# Connectors_GPIOs.net
KiCad netlist of a schematic drawn in Altium Designer
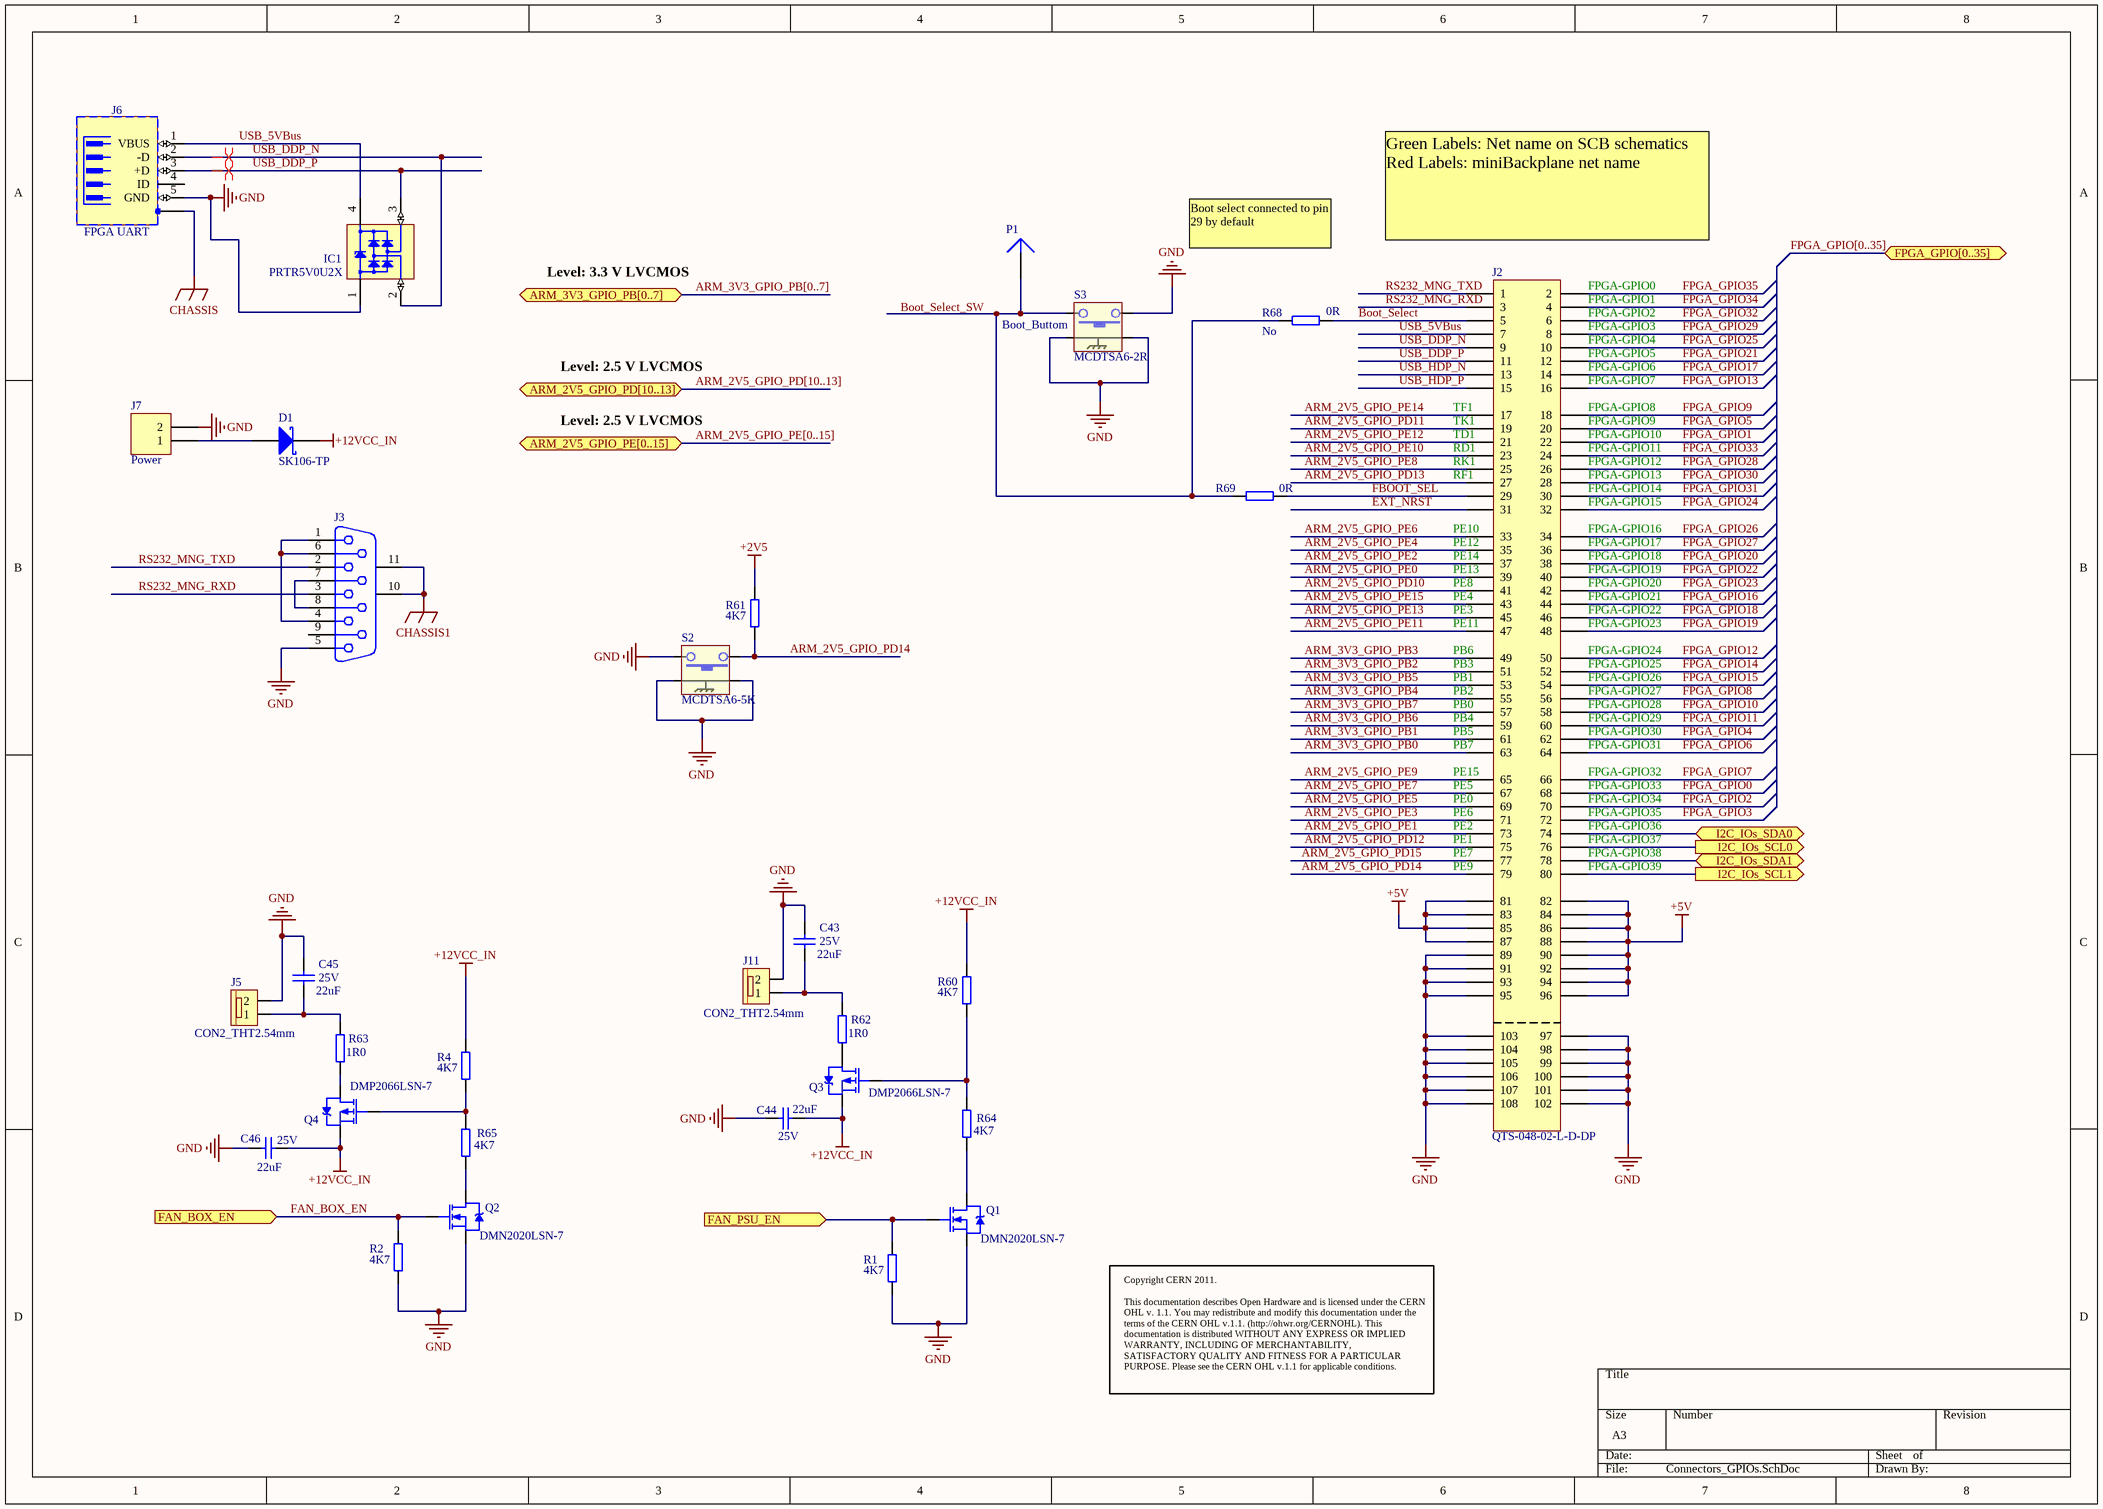
[diagram p0: Connectors_GPIOs.SchDoc]

(export (version "E")
  (design (tool "Eeschema 10.0.6"))
  (components
    (comp (ref "C43")
      (value "22uF")
      (footprint "CC3216-1206")
      (description "Capacitor")
      (fields
        (field (name "TOLERANCE") "±10%")
        (field (name "VOLTAGE") "25V")
        (field (name "Comment") "22uF 25V")
        (field (name "PUBLISHER") "Altium Limited")
      )
      (libsource (lib "wr_switch") (part "Cap"))
    )
    (comp (ref "C44")
      (value "22uF")
      (footprint "CC3216-1206")
      (description "Capacitor")
      (fields
        (field (name "TOLERANCE") "±10%")
        (field (name "VOLTAGE") "25V")
        (field (name "Comment") "22uF 25V")
        (field (name "PUBLISHER") "Altium Limited")
      )
      (libsource (lib "wr_switch") (part "Cap"))
    )
    (comp (ref "C45")
      (value "22uF")
      (footprint "CC3216-1206")
      (description "Capacitor")
      (fields
        (field (name "TOLERANCE") "±10%")
        (field (name "VOLTAGE") "25V")
        (field (name "Comment") "22uF 25V")
        (field (name "PUBLISHER") "Altium Limited")
      )
      (libsource (lib "wr_switch") (part "Cap"))
    )
    (comp (ref "C46")
      (value "22uF")
      (footprint "CC3216-1206")
      (description "Capacitor")
      (fields
        (field (name "TOLERANCE") "±10%")
        (field (name "VOLTAGE") "25V")
        (field (name "Comment") "22uF 25V")
        (field (name "PUBLISHER") "Altium Limited")
      )
      (libsource (lib "wr_switch") (part "Cap"))
    )
    (comp (ref "D1")
      (value "SK106-TP")
      (footprint "7S_WR:DO-214AB/SMB-MCC")
      (description "Schottky Diode 10A 60V")
      (libsource (lib "wr_switch") (part "SK106-TP"))
    )
    (comp (ref "IC1")
      (value "PRTR5V0U2X")
      (footprint "7S_WR:SOT190P230X110-4N")
      (description "Ultra Low Capacitance Double Rail-to-Rail ESD Protection Diode")
      (fields
        (field (name "VOLTAGE") "5.5V")
        (field (name "MANUFACTURER") "PHILIPS NXP")
        (field (name "AUTHOR") "CERN DEM JLC")
      )
      (libsource (lib "wr_switch") (part "PRTR5V0U2X"))
    )
    (comp (ref "J2")
      (value "QTS-048-02-L-D-DP")
      (footprint "QTS-048-XX-X-D-DP-A")
      (description "High Speed Ground Plane Header")
      (libsource (lib "wr_switch") (part "QTS-048-01-L-D-DP"))
    )
    (comp (ref "J3")
      (value "D Connector 9")
      (footprint "7S_WR:DSUB1.385-2H9")
      (description "Receptacle Assembly, 9 Position, Right Angle")
      (fields (field (name "PUBLISHER") "Altium Limited"))
      (libsource (lib "Miscellaneous Connectors") (part "D Connector 9"))
    )
    (comp (ref "J5")
      (value "CON2_THT2.54mm")
      (footprint "Wurth_619_0xx")
      (description "Connector")
      (libsource (lib "wr_switch") (part "CON2_619_0xx"))
    )
    (comp (ref "J6")
      (value "FPGA UART")
      (footprint "7S_WR:TYCO_1734035-1")
      (description "5 Pin + 1 Shield USB Receptacle")
      (fields
        (field (name "PART NUMBER") "TYCO_1734035-1")
        (field (name "MANUFACTURER") "TYCO ELECTRONICS")
        (field (name "AUTHOR") "CERN DEM JLC")
      )
      (libsource (lib "Connectors") (part "Connector USB 5 Pin + 1Shield"))
    )
    (comp (ref "J7")
      (value "Power")
      (footprint "7S_WR:TYCO_794120_1")
      (description "Header, 2-Pin")
      (fields (field (name "PUBLISHER") "Altium Limited"))
      (libsource (lib "Miscellaneous Connectors") (part "Header 2"))
    )
    (comp (ref "J11")
      (value "CON2_THT2.54mm")
      (footprint "Wurth_619_0xx")
      (description "Connector")
      (libsource (lib "wr_switch") (part "CON2_619_0xx"))
    )
    (comp (ref "P1")
      (value "Boot_Buttom")
      (footprint "PIN1-RT-01T-1.0B(LF)")
      (description "Plug")
      (fields (field (name "PUBLISHER") "Altium Limited"))
      (libsource (lib "Miscellaneous Connectors") (part "Plug"))
    )
    (comp (ref "Q1")
      (value "DMN2020LSN-7")
      (footprint "7S_WR:SC-59-3")
      (description "N-Channel Power MOSFET")
      (fields (field (name "MANUFACTURER") "Diodes Inc.") (field (name "PUBLISHER") "Altium Limited"))
      (libsource (lib "wr_switch") (part "NMOS-2"))
    )
    (comp (ref "Q2")
      (value "DMN2020LSN-7")
      (footprint "7S_WR:SC-59-3")
      (description "N-Channel Power MOSFET")
      (fields (field (name "MANUFACTURER") "Diodes Inc.") (field (name "PUBLISHER") "Altium Limited"))
      (libsource (lib "wr_switch") (part "NMOS-2"))
    )
    (comp (ref "Q3")
      (value "DMP2066LSN-7")
      (footprint "SC-59-3")
      (description "P-Channel Enhancement MOSFET")
      (fields (field (name "MANUFACTURER") "Diodes Inc."))
      (libsource (lib "wr_switch") (part "PMOS-2-Reflexion"))
    )
    (comp (ref "Q4")
      (value "DMP2066LSN-7")
      (footprint "SC-59-3")
      (description "P-Channel Enhancement MOSFET")
      (fields (field (name "MANUFACTURER") "Diodes Inc."))
      (libsource (lib "wr_switch") (part "PMOS-2-Reflexion"))
    )
    (comp (ref "R1")
      (value "4K7")
      (footprint "0603")
      (description "SMD Resistor")
      (fields (field (name "TOLERANCE") "±1%"))
      (libsource (lib "wr_switch") (part "RES_SMD"))
    )
    (comp (ref "R2")
      (value "4K7")
      (footprint "0603")
      (description "SMD Resistor")
      (fields (field (name "TOLERANCE") "±1%"))
      (libsource (lib "wr_switch") (part "RES_SMD"))
    )
    (comp (ref "R4")
      (value "4K7")
      (footprint "0603")
      (description "SMD Resistor")
      (fields (field (name "TOLERANCE") "±1%"))
      (libsource (lib "wr_switch") (part "RES_SMD"))
    )
    (comp (ref "R60")
      (value "4K7")
      (footprint "0603")
      (description "SMD Resistor")
      (fields (field (name "TOLERANCE") "±1%"))
      (libsource (lib "wr_switch") (part "RES_SMD"))
    )
    (comp (ref "R61")
      (value "4K7")
      (footprint "0603")
      (description "SMD Resistor")
      (fields (field (name "TOLERANCE") "±1%"))
      (libsource (lib "wr_switch") (part "RES_SMD"))
    )
    (comp (ref "R62")
      (value "1R0")
      (footprint "CR3225-1210")
      (description "SMD Resistor")
      (fields (field (name "TOLERANCE") "±1%"))
      (libsource (lib "wr_switch") (part "RES_SMD"))
    )
    (comp (ref "R63")
      (value "1R0")
      (footprint "CR3225-1210")
      (description "SMD Resistor")
      (fields (field (name "TOLERANCE") "±1%"))
      (libsource (lib "wr_switch") (part "RES_SMD"))
    )
    (comp (ref "R64")
      (value "4K7")
      (footprint "0603")
      (description "SMD Resistor")
      (fields (field (name "TOLERANCE") "±1%"))
      (libsource (lib "wr_switch") (part "RES_SMD"))
    )
    (comp (ref "R65")
      (value "4K7")
      (footprint "0603")
      (description "SMD Resistor")
      (fields (field (name "TOLERANCE") "±1%"))
      (libsource (lib "wr_switch") (part "RES_SMD"))
    )
    (comp (ref "R68")
      (value "0R")
      (footprint "0603")
      (description "SMD Resistor")
      (fields (field (name "MOUNTED") "No"))
      (libsource (lib "wr_switch") (part "RES_SMD"))
    )
    (comp (ref "R69")
      (value "0R")
      (footprint "0603")
      (description "SMD Resistor")
      (libsource (lib "wr_switch") (part "RES_SMD"))
    )
    (comp (ref "S2")
      (value "MCDTSA6-5K")
      (footprint "MCDTSA6")
      (description "Push button SPNO Right Angle Through Hole")
      (libsource (lib "wr_switch") (part "MCDTSA6"))
    )
    (comp (ref "S3")
      (value "MCDTSA6-2R")
      (footprint "MCDTSA6")
      (description "Push button SPNO Right Angle Through Hole")
      (libsource (lib "wr_switch") (part "MCDTSA6"))
    )
  )
  (nets
    (net (code "1") (name "+2V5") (class "Default")
      (node (ref "R61") (pin "1") (pinfunction "1_1") (pintype "passive"))
    )
    (net (code "2") (name "+5V") (class "Default")
      (node (ref "J2") (pin "81") (pinfunction "81_81") (pintype "passive"))
      (node (ref "J2") (pin "82") (pinfunction "82_82") (pintype "passive"))
      (node (ref "J2") (pin "83") (pinfunction "83_83") (pintype "passive"))
      (node (ref "J2") (pin "84") (pinfunction "84_84") (pintype "passive"))
      (node (ref "J2") (pin "85") (pinfunction "85_85") (pintype "passive"))
      (node (ref "J2") (pin "86") (pinfunction "86_86") (pintype "passive"))
      (node (ref "J2") (pin "87") (pinfunction "87_87") (pintype "passive"))
      (node (ref "J2") (pin "88") (pinfunction "88_88") (pintype "passive"))
      (node (ref "J2") (pin "90") (pinfunction "90_90") (pintype "passive"))
      (node (ref "J2") (pin "92") (pinfunction "92_92") (pintype "passive"))
      (node (ref "J2") (pin "94") (pinfunction "94_94") (pintype "passive"))
      (node (ref "J2") (pin "96") (pinfunction "96_96") (pintype "passive"))
    )
    (net (code "3") (name "+12VCC_IN") (class "Default")
      (node (ref "C44") (pin "1") (pinfunction "1_1") (pintype "passive"))
      (node (ref "C46") (pin "1") (pinfunction "1_1") (pintype "passive"))
      (node (ref "D1") (pin "1") (pinfunction "K_1") (pintype "passive"))
      (node (ref "Q3") (pin "3") (pinfunction "S_3") (pintype "passive"))
      (node (ref "Q4") (pin "3") (pinfunction "S_3") (pintype "passive"))
      (node (ref "R4") (pin "1") (pinfunction "1_1") (pintype "passive"))
      (node (ref "R60") (pin "1") (pinfunction "1_1") (pintype "passive"))
    )
    (net (code "4") (name "/ARM_2V5_GPIO_PD10") (class "Default")
      (node (ref "J2") (pin "41") (pinfunction "41_41") (pintype "passive"))
    )
    (net (code "5") (name "/ARM_2V5_GPIO_PD11") (class "Default")
      (node (ref "J2") (pin "19") (pinfunction "19_19") (pintype "passive"))
    )
    (net (code "6") (name "/ARM_2V5_GPIO_PD12") (class "Default")
      (node (ref "J2") (pin "75") (pinfunction "75_75") (pintype "passive"))
    )
    (net (code "7") (name "/ARM_2V5_GPIO_PD13") (class "Default")
      (node (ref "J2") (pin "27") (pinfunction "27_27") (pintype "passive"))
    )
    (net (code "8") (name "/ARM_2V5_GPIO_PD14") (class "Default")
      (node (ref "J2") (pin "79") (pinfunction "79_79") (pintype "passive"))
      (node (ref "R61") (pin "2") (pinfunction "2_2") (pintype "passive"))
      (node (ref "S2") (pin "1") (pinfunction "1_1") (pintype "passive"))
    )
    (net (code "9") (name "/ARM_2V5_GPIO_PD15") (class "Default")
      (node (ref "J2") (pin "77") (pinfunction "77_77") (pintype "passive"))
    )
    (net (code "11") (name "/ARM_2V5_GPIO_PE0") (class "Default")
      (node (ref "J2") (pin "39") (pinfunction "39_39") (pintype "passive"))
    )
    (net (code "12") (name "/ARM_2V5_GPIO_PE1") (class "Default")
      (node (ref "J2") (pin "73") (pinfunction "73_73") (pintype "passive"))
    )
    (net (code "13") (name "/ARM_2V5_GPIO_PE2") (class "Default")
      (node (ref "J2") (pin "37") (pinfunction "37_37") (pintype "passive"))
    )
    (net (code "14") (name "/ARM_2V5_GPIO_PE3") (class "Default")
      (node (ref "J2") (pin "71") (pinfunction "71_71") (pintype "passive"))
    )
    (net (code "15") (name "/ARM_2V5_GPIO_PE4") (class "Default")
      (node (ref "J2") (pin "35") (pinfunction "35_35") (pintype "passive"))
    )
    (net (code "16") (name "/ARM_2V5_GPIO_PE5") (class "Default")
      (node (ref "J2") (pin "69") (pinfunction "69_69") (pintype "passive"))
    )
    (net (code "17") (name "/ARM_2V5_GPIO_PE6") (class "Default")
      (node (ref "J2") (pin "33") (pinfunction "33_33") (pintype "passive"))
    )
    (net (code "18") (name "/ARM_2V5_GPIO_PE7") (class "Default")
      (node (ref "J2") (pin "67") (pinfunction "67_67") (pintype "passive"))
    )
    (net (code "19") (name "/ARM_2V5_GPIO_PE8") (class "Default")
      (node (ref "J2") (pin "25") (pinfunction "25_25") (pintype "passive"))
    )
    (net (code "20") (name "/ARM_2V5_GPIO_PE9") (class "Default")
      (node (ref "J2") (pin "65") (pinfunction "65_65") (pintype "passive"))
    )
    (net (code "21") (name "/ARM_2V5_GPIO_PE10") (class "Default")
      (node (ref "J2") (pin "23") (pinfunction "23_23") (pintype "passive"))
    )
    (net (code "22") (name "/ARM_2V5_GPIO_PE11") (class "Default")
      (node (ref "J2") (pin "47") (pinfunction "47_47") (pintype "passive"))
    )
    (net (code "23") (name "/ARM_2V5_GPIO_PE12") (class "Default")
      (node (ref "J2") (pin "21") (pinfunction "21_21") (pintype "passive"))
    )
    (net (code "24") (name "/ARM_2V5_GPIO_PE13") (class "Default")
      (node (ref "J2") (pin "45") (pinfunction "45_45") (pintype "passive"))
    )
    (net (code "25") (name "/ARM_2V5_GPIO_PE14") (class "Default")
      (node (ref "J2") (pin "17") (pinfunction "17_17") (pintype "passive"))
    )
    (net (code "26") (name "/ARM_2V5_GPIO_PE15") (class "Default")
      (node (ref "J2") (pin "43") (pinfunction "43_43") (pintype "passive"))
    )
    (net (code "28") (name "/ARM_3V3_GPIO_PB0") (class "Default")
      (node (ref "J2") (pin "63") (pinfunction "63_63") (pintype "passive"))
    )
    (net (code "29") (name "/ARM_3V3_GPIO_PB1") (class "Default")
      (node (ref "J2") (pin "61") (pinfunction "61_61") (pintype "passive"))
    )
    (net (code "30") (name "/ARM_3V3_GPIO_PB2") (class "Default")
      (node (ref "J2") (pin "51") (pinfunction "51_51") (pintype "passive"))
    )
    (net (code "31") (name "/ARM_3V3_GPIO_PB3") (class "Default")
      (node (ref "J2") (pin "49") (pinfunction "49_49") (pintype "passive"))
    )
    (net (code "32") (name "/ARM_3V3_GPIO_PB4") (class "Default")
      (node (ref "J2") (pin "55") (pinfunction "55_55") (pintype "passive"))
    )
    (net (code "33") (name "/ARM_3V3_GPIO_PB5") (class "Default")
      (node (ref "J2") (pin "53") (pinfunction "53_53") (pintype "passive"))
    )
    (net (code "34") (name "/ARM_3V3_GPIO_PB6") (class "Default")
      (node (ref "J2") (pin "59") (pinfunction "59_59") (pintype "passive"))
    )
    (net (code "35") (name "/ARM_3V3_GPIO_PB7") (class "Default")
      (node (ref "J2") (pin "57") (pinfunction "57_57") (pintype "passive"))
    )
    (net (code "37") (name "/Boot_Select") (class "Default")
      (node (ref "J2") (pin "5") (pinfunction "5_5") (pintype "passive"))
      (node (ref "R68") (pin "2") (pinfunction "2_2") (pintype "passive"))
    )
    (net (code "39") (name "/EXT_NRST") (class "Default")
      (node (ref "J2") (pin "31") (pinfunction "31_31") (pintype "passive"))
    )
    (net (code "40") (name "/FAN_BOX_EN") (class "Default")
      (node (ref "Q2") (pin "1") (pinfunction "G_1") (pintype "passive"))
      (node (ref "R2") (pin "1") (pinfunction "1_1") (pintype "passive"))
    )
    (net (code "41") (name "/FAN_PSU_EN") (class "Default")
      (node (ref "Q1") (pin "1") (pinfunction "G_1") (pintype "passive"))
      (node (ref "R1") (pin "1") (pinfunction "1_1") (pintype "passive"))
    )
    (net (code "42") (name "/FBOOT_SEL") (class "Default")
      (node (ref "J2") (pin "29") (pinfunction "29_29") (pintype "passive"))
      (node (ref "R69") (pin "2") (pinfunction "2_2") (pintype "passive"))
    )
    (net (code "43") (name "/FPGA-GPIO36") (class "Default")
      (node (ref "J2") (pin "74") (pinfunction "74_74") (pintype "passive"))
    )
    (net (code "44") (name "/FPGA-GPIO37") (class "Default")
      (node (ref "J2") (pin "76") (pinfunction "76_76") (pintype "passive"))
    )
    (net (code "45") (name "/FPGA-GPIO38") (class "Default")
      (node (ref "J2") (pin "78") (pinfunction "78_78") (pintype "passive"))
    )
    (net (code "46") (name "/FPGA-GPIO39") (class "Default")
      (node (ref "J2") (pin "80") (pinfunction "80_80") (pintype "passive"))
    )
    (net (code "47") (name "/FPGA_GPIO0") (class "Default")
      (node (ref "J2") (pin "68") (pinfunction "68_68") (pintype "passive"))
    )
    (net (code "48") (name "/FPGA_GPIO1") (class "Default")
      (node (ref "J2") (pin "22") (pinfunction "22_22") (pintype "passive"))
    )
    (net (code "49") (name "/FPGA_GPIO2") (class "Default")
      (node (ref "J2") (pin "70") (pinfunction "70_70") (pintype "passive"))
    )
    (net (code "50") (name "/FPGA_GPIO3") (class "Default")
      (node (ref "J2") (pin "72") (pinfunction "72_72") (pintype "passive"))
    )
    (net (code "51") (name "/FPGA_GPIO4") (class "Default")
      (node (ref "J2") (pin "62") (pinfunction "62_62") (pintype "passive"))
    )
    (net (code "52") (name "/FPGA_GPIO5") (class "Default")
      (node (ref "J2") (pin "20") (pinfunction "20_20") (pintype "passive"))
    )
    (net (code "53") (name "/FPGA_GPIO6") (class "Default")
      (node (ref "J2") (pin "64") (pinfunction "64_64") (pintype "passive"))
    )
    (net (code "54") (name "/FPGA_GPIO7") (class "Default")
      (node (ref "J2") (pin "66") (pinfunction "66_66") (pintype "passive"))
    )
    (net (code "55") (name "/FPGA_GPIO8") (class "Default")
      (node (ref "J2") (pin "56") (pinfunction "56_56") (pintype "passive"))
    )
    (net (code "56") (name "/FPGA_GPIO9") (class "Default")
      (node (ref "J2") (pin "18") (pinfunction "18_18") (pintype "passive"))
    )
    (net (code "57") (name "/FPGA_GPIO10") (class "Default")
      (node (ref "J2") (pin "58") (pinfunction "58_58") (pintype "passive"))
    )
    (net (code "58") (name "/FPGA_GPIO11") (class "Default")
      (node (ref "J2") (pin "60") (pinfunction "60_60") (pintype "passive"))
    )
    (net (code "59") (name "/FPGA_GPIO12") (class "Default")
      (node (ref "J2") (pin "50") (pinfunction "50_50") (pintype "passive"))
    )
    (net (code "60") (name "/FPGA_GPIO13") (class "Default")
      (node (ref "J2") (pin "16") (pinfunction "16_16") (pintype "passive"))
    )
    (net (code "61") (name "/FPGA_GPIO14") (class "Default")
      (node (ref "J2") (pin "52") (pinfunction "52_52") (pintype "passive"))
    )
    (net (code "62") (name "/FPGA_GPIO15") (class "Default")
      (node (ref "J2") (pin "54") (pinfunction "54_54") (pintype "passive"))
    )
    (net (code "63") (name "/FPGA_GPIO16") (class "Default")
      (node (ref "J2") (pin "44") (pinfunction "44_44") (pintype "passive"))
    )
    (net (code "64") (name "/FPGA_GPIO17") (class "Default")
      (node (ref "J2") (pin "14") (pinfunction "14_14") (pintype "passive"))
    )
    (net (code "65") (name "/FPGA_GPIO18") (class "Default")
      (node (ref "J2") (pin "46") (pinfunction "46_46") (pintype "passive"))
    )
    (net (code "66") (name "/FPGA_GPIO19") (class "Default")
      (node (ref "J2") (pin "48") (pinfunction "48_48") (pintype "passive"))
    )
    (net (code "67") (name "/FPGA_GPIO20") (class "Default")
      (node (ref "J2") (pin "38") (pinfunction "38_38") (pintype "passive"))
    )
    (net (code "68") (name "/FPGA_GPIO21") (class "Default")
      (node (ref "J2") (pin "12") (pinfunction "12_12") (pintype "passive"))
    )
    (net (code "69") (name "/FPGA_GPIO22") (class "Default")
      (node (ref "J2") (pin "40") (pinfunction "40_40") (pintype "passive"))
    )
    (net (code "70") (name "/FPGA_GPIO23") (class "Default")
      (node (ref "J2") (pin "42") (pinfunction "42_42") (pintype "passive"))
    )
    (net (code "71") (name "/FPGA_GPIO24") (class "Default")
      (node (ref "J2") (pin "32") (pinfunction "32_32") (pintype "passive"))
    )
    (net (code "72") (name "/FPGA_GPIO25") (class "Default")
      (node (ref "J2") (pin "10") (pinfunction "10_10") (pintype "passive"))
    )
    (net (code "73") (name "/FPGA_GPIO26") (class "Default")
      (node (ref "J2") (pin "34") (pinfunction "34_34") (pintype "passive"))
    )
    (net (code "74") (name "/FPGA_GPIO27") (class "Default")
      (node (ref "J2") (pin "36") (pinfunction "36_36") (pintype "passive"))
    )
    (net (code "75") (name "/FPGA_GPIO28") (class "Default")
      (node (ref "J2") (pin "26") (pinfunction "26_26") (pintype "passive"))
    )
    (net (code "76") (name "/FPGA_GPIO29") (class "Default")
      (node (ref "J2") (pin "8") (pinfunction "8_8") (pintype "passive"))
    )
    (net (code "77") (name "/FPGA_GPIO30") (class "Default")
      (node (ref "J2") (pin "28") (pinfunction "28_28") (pintype "passive"))
    )
    (net (code "78") (name "/FPGA_GPIO31") (class "Default")
      (node (ref "J2") (pin "30") (pinfunction "30_30") (pintype "passive"))
    )
    (net (code "79") (name "/FPGA_GPIO32") (class "Default")
      (node (ref "J2") (pin "6") (pinfunction "6_6") (pintype "passive"))
    )
    (net (code "80") (name "/FPGA_GPIO33") (class "Default")
      (node (ref "J2") (pin "24") (pinfunction "24_24") (pintype "passive"))
    )
    (net (code "81") (name "/FPGA_GPIO34") (class "Default")
      (node (ref "J2") (pin "4") (pinfunction "4_4") (pintype "passive"))
    )
    (net (code "82") (name "/FPGA_GPIO35") (class "Default")
      (node (ref "J2") (pin "2") (pinfunction "2_2") (pintype "passive"))
    )
    (net (code "84") (name "/RS232_MNG_RXD") (class "Default")
      (node (ref "J2") (pin "3") (pinfunction "3_3") (pintype "passive"))
      (node (ref "J3") (pin "3") (pinfunction "3_3") (pintype "passive"))
    )
    (net (code "85") (name "/RS232_MNG_TXD") (class "Default")
      (node (ref "J2") (pin "1") (pinfunction "1_1") (pintype "passive"))
      (node (ref "J3") (pin "2") (pinfunction "2_2") (pintype "passive"))
    )
    (net (code "86") (name "/USB_5VBus") (class "Default")
      (node (ref "IC1") (pin "4") (pinfunction "VCC_4") (pintype "power_in"))
      (node (ref "J2") (pin "7") (pinfunction "7_7") (pintype "passive"))
      (node (ref "J6") (pin "1") (pinfunction "VBUS_1") (pintype "bidirectional"))
    )
    (net (code "87") (name "/USB_DDP_N") (class "Default")
      (node (ref "IC1") (pin "2") (pinfunction "I/O1_2") (pintype "bidirectional"))
      (node (ref "J2") (pin "9") (pinfunction "9_9") (pintype "passive"))
      (node (ref "J6") (pin "2") (pinfunction "-D_2") (pintype "bidirectional"))
    )
    (net (code "88") (name "/USB_DDP_P") (class "Default")
      (node (ref "IC1") (pin "3") (pinfunction "I/O2_3") (pintype "bidirectional"))
      (node (ref "J2") (pin "11") (pinfunction "11_11") (pintype "passive"))
      (node (ref "J6") (pin "3") (pinfunction "+D_3") (pintype "bidirectional"))
    )
    (net (code "89") (name "/USB_HDP_N") (class "Default")
      (node (ref "J2") (pin "13") (pinfunction "13_13") (pintype "passive"))
    )
    (net (code "90") (name "/USB_HDP_P") (class "Default")
      (node (ref "J2") (pin "15") (pinfunction "15_15") (pintype "passive"))
    )
    (net (code "91") (name "CHASSIS") (class "Default")
      (node (ref "J6") (pin "6") (pinfunction "SH_6") (pintype "power_in"))
    )
    (net (code "92") (name "CHASSIS1") (class "Default")
      (node (ref "J3") (pin "10") (pinfunction "MH1_10") (pintype "passive"))
      (node (ref "J3") (pin "11") (pinfunction "MH2_11") (pintype "passive"))
    )
    (net (code "93") (name "GND") (class "Default")
      (node (ref "C43") (pin "2") (pinfunction "2_2") (pintype "passive"))
      (node (ref "C44") (pin "2") (pinfunction "2_2") (pintype "passive"))
      (node (ref "C45") (pin "2") (pinfunction "2_2") (pintype "passive"))
      (node (ref "C46") (pin "2") (pinfunction "2_2") (pintype "passive"))
      (node (ref "IC1") (pin "1") (pinfunction "GND_1") (pintype "power_in"))
      (node (ref "J11") (pin "2") (pinfunction "2_2") (pintype "passive"))
      (node (ref "J2") (pin "100") (pinfunction "100_100") (pintype "passive"))
      (node (ref "J2") (pin "101") (pinfunction "101_101") (pintype "passive"))
      (node (ref "J2") (pin "102") (pinfunction "102_102") (pintype "passive"))
      (node (ref "J2") (pin "103") (pinfunction "103_103") (pintype "passive"))
      (node (ref "J2") (pin "104") (pinfunction "104_104") (pintype "passive"))
      (node (ref "J2") (pin "105") (pinfunction "105_105") (pintype "passive"))
      (node (ref "J2") (pin "106") (pinfunction "106_106") (pintype "passive"))
      (node (ref "J2") (pin "107") (pinfunction "107_107") (pintype "passive"))
      (node (ref "J2") (pin "108") (pinfunction "108_108") (pintype "passive"))
      (node (ref "J2") (pin "89") (pinfunction "89_89") (pintype "passive"))
      (node (ref "J2") (pin "91") (pinfunction "91_91") (pintype "passive"))
      (node (ref "J2") (pin "93") (pinfunction "93_93") (pintype "passive"))
      (node (ref "J2") (pin "95") (pinfunction "95_95") (pintype "passive"))
      (node (ref "J2") (pin "97") (pinfunction "97_97") (pintype "passive"))
      (node (ref "J2") (pin "98") (pinfunction "98_98") (pintype "passive"))
      (node (ref "J2") (pin "99") (pinfunction "99_99") (pintype "passive"))
      (node (ref "J3") (pin "5") (pinfunction "5_5") (pintype "passive"))
      (node (ref "J5") (pin "2") (pinfunction "2_2") (pintype "passive"))
      (node (ref "J6") (pin "5") (pinfunction "GND_5") (pintype "bidirectional"))
      (node (ref "J7") (pin "2") (pinfunction "2_2") (pintype "passive"))
      (node (ref "Q1") (pin "3") (pinfunction "S_3") (pintype "passive"))
      (node (ref "Q2") (pin "3") (pinfunction "S_3") (pintype "passive"))
      (node (ref "R1") (pin "2") (pinfunction "2_2") (pintype "passive"))
      (node (ref "R2") (pin "2") (pinfunction "2_2") (pintype "passive"))
      (node (ref "S2") (pin "2") (pinfunction "2_2") (pintype "passive"))
      (node (ref "S2") (pin "3") (pinfunction "3_3") (pintype "power_in"))
      (node (ref "S2") (pin "4") (pinfunction "4_4") (pintype "power_in"))
      (node (ref "S3") (pin "1") (pinfunction "1_1") (pintype "passive"))
      (node (ref "S3") (pin "3") (pinfunction "3_3") (pintype "power_in"))
      (node (ref "S3") (pin "4") (pinfunction "4_4") (pintype "power_in"))
    )
    (net (code "94") (name "Net-(C43-Pad1)") (class "Default")
      (node (ref "C43") (pin "1") (pinfunction "1_1") (pintype "passive"))
      (node (ref "J11") (pin "1") (pinfunction "1_1") (pintype "passive"))
      (node (ref "R62") (pin "2") (pinfunction "2_2") (pintype "passive"))
    )
    (net (code "95") (name "Net-(C45-Pad1)") (class "Default")
      (node (ref "C45") (pin "1") (pinfunction "1_1") (pintype "passive"))
      (node (ref "J5") (pin "1") (pinfunction "1_1") (pintype "passive"))
      (node (ref "R63") (pin "2") (pinfunction "2_2") (pintype "passive"))
    )
    (net (code "96") (name "Net-(D1-A)") (class "Default")
      (node (ref "D1") (pin "2") (pinfunction "A_2") (pintype "passive"))
      (node (ref "J7") (pin "1") (pinfunction "1_1") (pintype "passive"))
    )
    (net (code "97") (name "Net-(J3-Pad1)") (class "Default")
      (node (ref "J3") (pin "1") (pinfunction "1_1") (pintype "passive"))
      (node (ref "J3") (pin "4") (pinfunction "4_4") (pintype "passive"))
      (node (ref "J3") (pin "6") (pinfunction "6_6") (pintype "passive"))
    )
    (net (code "98") (name "Net-(J3-Pad7)") (class "Default")
      (node (ref "J3") (pin "7") (pinfunction "7_7") (pintype "passive"))
      (node (ref "J3") (pin "8") (pinfunction "8_8") (pintype "passive"))
    )
    (net (code "99") (name "Net-(P1-Pad1)") (class "Default")
      (node (ref "P1") (pin "1") (pinfunction "1_1") (pintype "passive"))
      (node (ref "R68") (pin "1") (pinfunction "1_1") (pintype "passive"))
      (node (ref "R69") (pin "1") (pinfunction "1_1") (pintype "passive"))
      (node (ref "S3") (pin "2") (pinfunction "2_2") (pintype "passive"))
    )
    (net (code "100") (name "Net-(Q1-D)") (class "Default")
      (node (ref "Q1") (pin "2") (pinfunction "D_2") (pintype "passive"))
      (node (ref "R64") (pin "2") (pinfunction "2_2") (pintype "passive"))
    )
    (net (code "101") (name "Net-(Q2-D)") (class "Default")
      (node (ref "Q2") (pin "2") (pinfunction "D_2") (pintype "passive"))
      (node (ref "R65") (pin "2") (pinfunction "2_2") (pintype "passive"))
    )
    (net (code "102") (name "Net-(Q3-D)") (class "Default")
      (node (ref "Q3") (pin "2") (pinfunction "D_2") (pintype "passive"))
      (node (ref "R62") (pin "1") (pinfunction "1_1") (pintype "passive"))
    )
    (net (code "103") (name "Net-(Q3-G)") (class "Default")
      (node (ref "Q3") (pin "1") (pinfunction "G_1") (pintype "passive"))
      (node (ref "R60") (pin "2") (pinfunction "2_2") (pintype "passive"))
      (node (ref "R64") (pin "1") (pinfunction "1_1") (pintype "passive"))
    )
    (net (code "104") (name "Net-(Q4-D)") (class "Default")
      (node (ref "Q4") (pin "2") (pinfunction "D_2") (pintype "passive"))
      (node (ref "R63") (pin "1") (pinfunction "1_1") (pintype "passive"))
    )
    (net (code "105") (name "Net-(Q4-G)") (class "Default")
      (node (ref "Q4") (pin "1") (pinfunction "G_1") (pintype "passive"))
      (node (ref "R4") (pin "2") (pinfunction "2_2") (pintype "passive"))
      (node (ref "R65") (pin "1") (pinfunction "1_1") (pintype "passive"))
    )
    (net (code "106") (name "unconnected-(J3-Pad9)") (class "Default")
      (node (ref "J3") (pin "9") (pinfunction "9_9") (pintype "passive"))
    )
    (net (code "107") (name "unconnected-(J6-ID-Pad4)") (class "Default")
      (node (ref "J6") (pin "4") (pinfunction "ID_4") (pintype "passive"))
    )
  )
)
